# ADC_Input.net
KiCad netlist of a schematic drawn in Altium Designer
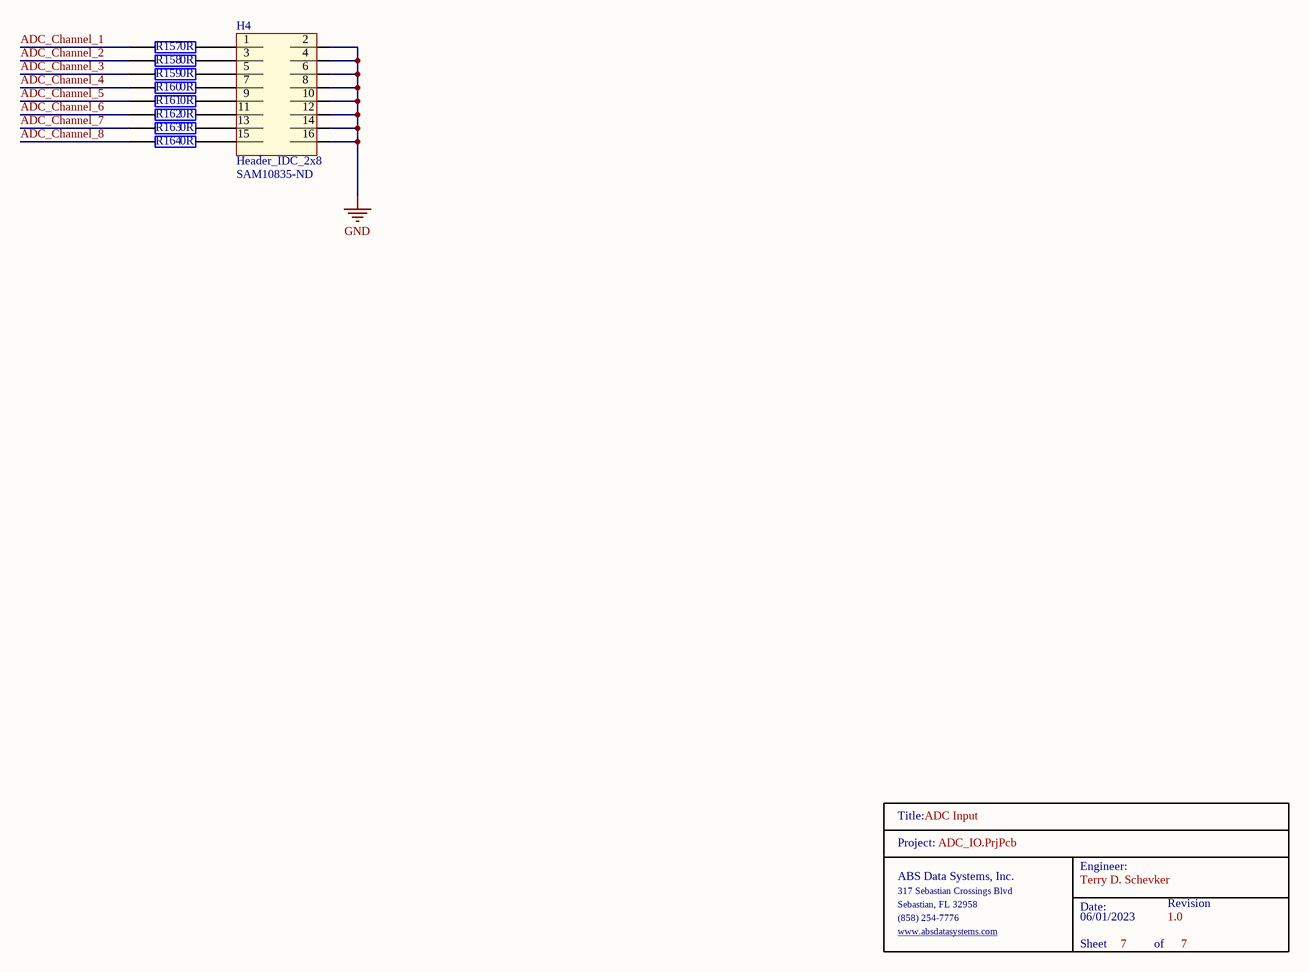
[diagram p0: ADC_Input.SchDoc]

(export (version "E")
  (design (tool "Eeschema 10.0.6"))
  (components
    (comp (ref "H4")
      (value "Header_IDC_2x8")
      (footprint "HEADER16")
      (description "16 Pin 2x8 Through Hold IDC Connector")
      (fields
        (field (name "MANUFACTURER") "Samtec")
        (field (name "MANUFACTURER PART NUMBER") "TST-108-01-G-D")
        (field (name "SUPPLIER PART NUMBER 1") "SAM10835-ND")
      )
      (libsource (lib "Misc") (part "Header_IDC_2x8"))
    )
    (comp (ref "R157")
      (value "0R")
      (footprint "0603")
      (description "YAGEO 0603 0 ohm")
      (fields
        (field (name "MOUSER PART NUMBER") "603-RC0603JR-070RL")
        (field (name "MANUFACTURER_PART_NUMBER") "RC0603JR-070RL")
      )
      (libsource (lib "Resistors") (part "RC0603JR-070RL"))
    )
    (comp (ref "R158")
      (value "0R")
      (footprint "0603")
      (description "YAGEO 0603 0 ohm")
      (fields
        (field (name "MOUSER PART NUMBER") "603-RC0603JR-070RL")
        (field (name "MANUFACTURER_PART_NUMBER") "RC0603JR-070RL")
      )
      (libsource (lib "Resistors") (part "RC0603JR-070RL"))
    )
    (comp (ref "R159")
      (value "0R")
      (footprint "0603")
      (description "YAGEO 0603 0 ohm")
      (fields
        (field (name "MOUSER PART NUMBER") "603-RC0603JR-070RL")
        (field (name "MANUFACTURER_PART_NUMBER") "RC0603JR-070RL")
      )
      (libsource (lib "Resistors") (part "RC0603JR-070RL"))
    )
    (comp (ref "R160")
      (value "0R")
      (footprint "0603")
      (description "YAGEO 0603 0 ohm")
      (fields
        (field (name "MOUSER PART NUMBER") "603-RC0603JR-070RL")
        (field (name "MANUFACTURER_PART_NUMBER") "RC0603JR-070RL")
      )
      (libsource (lib "Resistors") (part "RC0603JR-070RL"))
    )
    (comp (ref "R161")
      (value "0R")
      (footprint "0603")
      (description "YAGEO 0603 0 ohm")
      (fields
        (field (name "MOUSER PART NUMBER") "603-RC0603JR-070RL")
        (field (name "MANUFACTURER_PART_NUMBER") "RC0603JR-070RL")
      )
      (libsource (lib "Resistors") (part "RC0603JR-070RL"))
    )
    (comp (ref "R162")
      (value "0R")
      (footprint "0603")
      (description "YAGEO 0603 0 ohm")
      (fields
        (field (name "MOUSER PART NUMBER") "603-RC0603JR-070RL")
        (field (name "MANUFACTURER_PART_NUMBER") "RC0603JR-070RL")
      )
      (libsource (lib "Resistors") (part "RC0603JR-070RL"))
    )
    (comp (ref "R163")
      (value "0R")
      (footprint "0603")
      (description "YAGEO 0603 0 ohm")
      (fields
        (field (name "MOUSER PART NUMBER") "603-RC0603JR-070RL")
        (field (name "MANUFACTURER_PART_NUMBER") "RC0603JR-070RL")
      )
      (libsource (lib "Resistors") (part "RC0603JR-070RL"))
    )
    (comp (ref "R164")
      (value "0R")
      (footprint "0603")
      (description "YAGEO 0603 0 ohm")
      (fields
        (field (name "MOUSER PART NUMBER") "603-RC0603JR-070RL")
        (field (name "MANUFACTURER_PART_NUMBER") "RC0603JR-070RL")
      )
      (libsource (lib "Resistors") (part "RC0603JR-070RL"))
    )
    (comp (ref "TitleBlock_7") (value "TitleBlock") (libsource (lib "Misc") (part "TitleBlock")))
  )
  (nets
    (net (code "1") (name "/ADC_Channel_1") (class "Default")
      (node (ref "R157") (pin "1") (pinfunction "1_1") (pintype "passive"))
    )
    (net (code "2") (name "/ADC_Channel_2") (class "Default")
      (node (ref "R158") (pin "1") (pinfunction "1_1") (pintype "passive"))
    )
    (net (code "3") (name "/ADC_Channel_3") (class "Default")
      (node (ref "R159") (pin "1") (pinfunction "1_1") (pintype "passive"))
    )
    (net (code "4") (name "/ADC_Channel_4") (class "Default")
      (node (ref "R160") (pin "1") (pinfunction "1_1") (pintype "passive"))
    )
    (net (code "5") (name "/ADC_Channel_5") (class "Default")
      (node (ref "R161") (pin "1") (pinfunction "1_1") (pintype "passive"))
    )
    (net (code "6") (name "/ADC_Channel_6") (class "Default")
      (node (ref "R162") (pin "1") (pinfunction "1_1") (pintype "passive"))
    )
    (net (code "7") (name "/ADC_Channel_7") (class "Default")
      (node (ref "R163") (pin "1") (pinfunction "1_1") (pintype "passive"))
    )
    (net (code "8") (name "/ADC_Channel_8") (class "Default")
      (node (ref "R164") (pin "1") (pinfunction "1_1") (pintype "passive"))
    )
    (net (code "9") (name "GND") (class "Default")
      (node (ref "H4") (pin "10") (pinfunction "10_10") (pintype "passive"))
      (node (ref "H4") (pin "12") (pinfunction "12_12") (pintype "passive"))
      (node (ref "H4") (pin "14") (pinfunction "14_14") (pintype "passive"))
      (node (ref "H4") (pin "16") (pinfunction "16_16") (pintype "passive"))
      (node (ref "H4") (pin "2") (pinfunction "2_2") (pintype "passive"))
      (node (ref "H4") (pin "4") (pinfunction "4_4") (pintype "passive"))
      (node (ref "H4") (pin "6") (pinfunction "6_6") (pintype "passive"))
      (node (ref "H4") (pin "8") (pinfunction "8_8") (pintype "passive"))
    )
    (net (code "10") (name "Net-(H4-Pad1)") (class "Default")
      (node (ref "H4") (pin "1") (pinfunction "1_1") (pintype "passive"))
      (node (ref "R157") (pin "2") (pinfunction "2_2") (pintype "passive"))
    )
    (net (code "11") (name "Net-(H4-Pad3)") (class "Default")
      (node (ref "H4") (pin "3") (pinfunction "3_3") (pintype "passive"))
      (node (ref "R158") (pin "2") (pinfunction "2_2") (pintype "passive"))
    )
    (net (code "12") (name "Net-(H4-Pad5)") (class "Default")
      (node (ref "H4") (pin "5") (pinfunction "5_5") (pintype "passive"))
      (node (ref "R159") (pin "2") (pinfunction "2_2") (pintype "passive"))
    )
    (net (code "13") (name "Net-(H4-Pad7)") (class "Default")
      (node (ref "H4") (pin "7") (pinfunction "7_7") (pintype "passive"))
      (node (ref "R160") (pin "2") (pinfunction "2_2") (pintype "passive"))
    )
    (net (code "14") (name "Net-(H4-Pad9)") (class "Default")
      (node (ref "H4") (pin "9") (pinfunction "9_9") (pintype "passive"))
      (node (ref "R161") (pin "2") (pinfunction "2_2") (pintype "passive"))
    )
    (net (code "15") (name "Net-(H4-Pad11)") (class "Default")
      (node (ref "H4") (pin "11") (pinfunction "11_11") (pintype "passive"))
      (node (ref "R162") (pin "2") (pinfunction "2_2") (pintype "passive"))
    )
    (net (code "16") (name "Net-(H4-Pad13)") (class "Default")
      (node (ref "H4") (pin "13") (pinfunction "13_13") (pintype "passive"))
      (node (ref "R163") (pin "2") (pinfunction "2_2") (pintype "passive"))
    )
    (net (code "17") (name "Net-(H4-Pad15)") (class "Default")
      (node (ref "H4") (pin "15") (pinfunction "15_15") (pintype "passive"))
      (node (ref "R164") (pin "2") (pinfunction "2_2") (pintype "passive"))
    )
  )
)
